# Trepanat_Sensors_2.net
KiCad netlist of a schematic drawn in Altium Designer
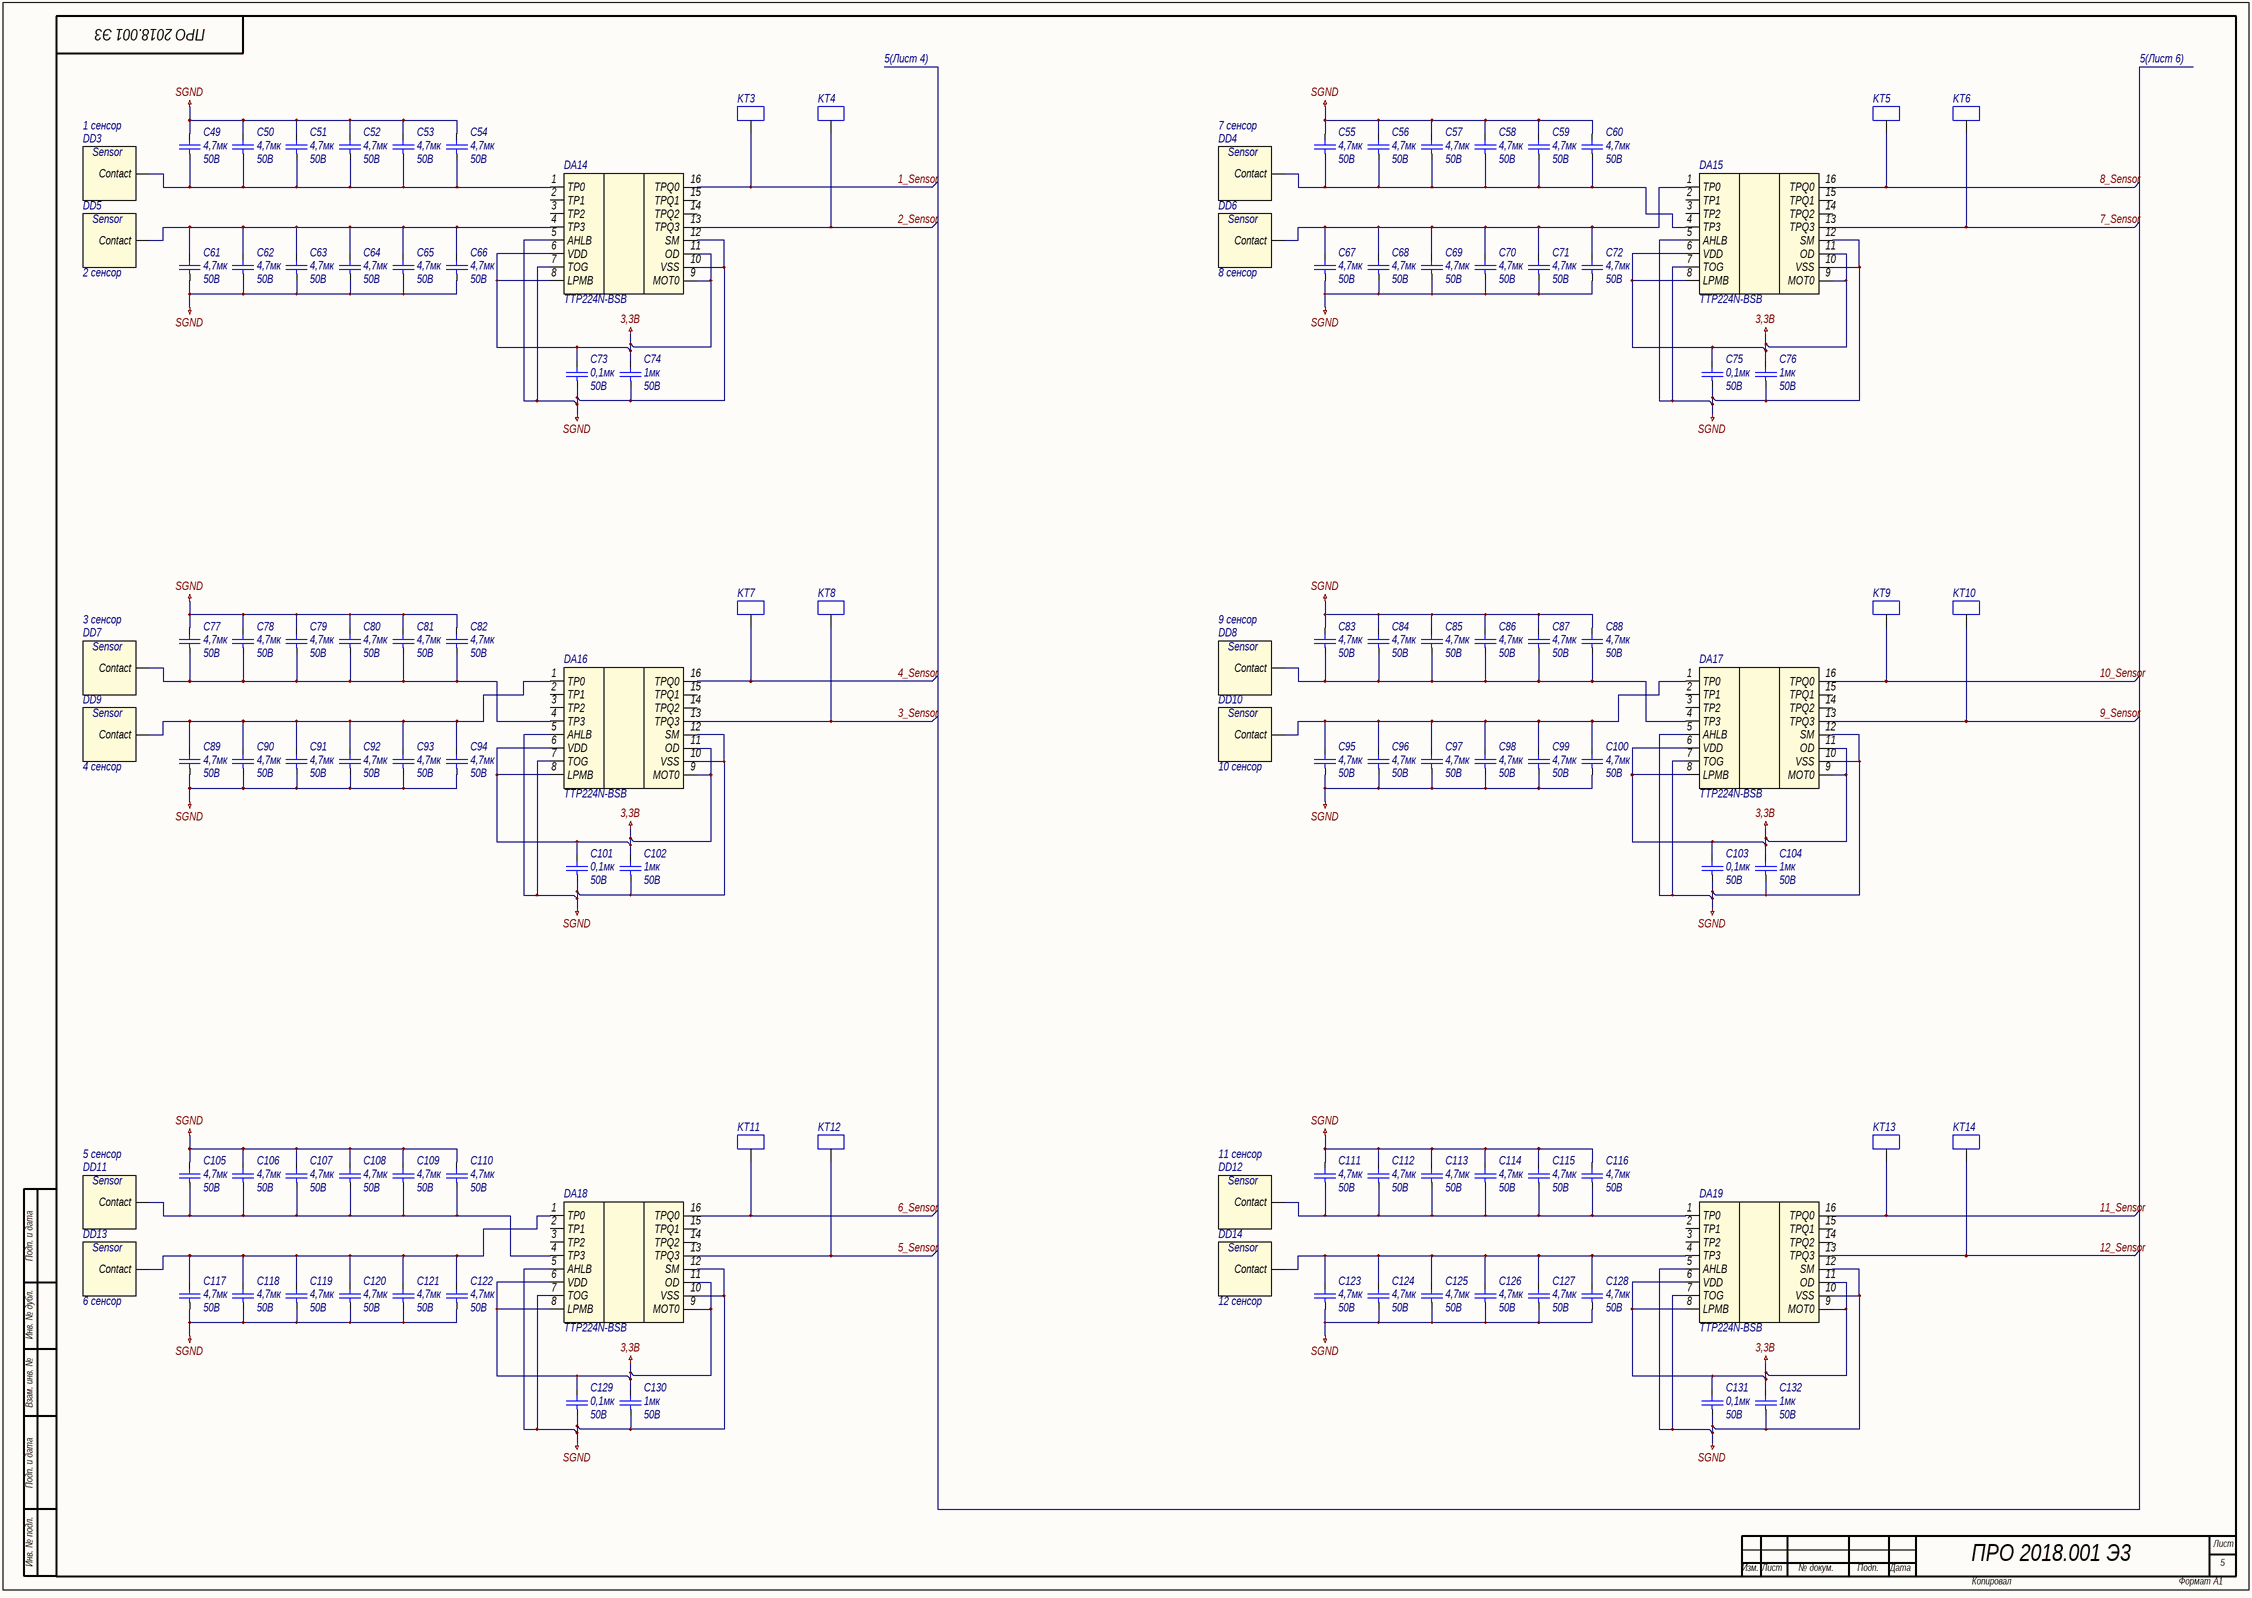
[diagram p0: Trepanat_Sensors_2.SchDoc]

(export (version "E")
  (design (tool "Eeschema 10.0.6"))
  (components
    (comp (ref "C49")
      (value "4,7мк")
      (footprint "ZabugorLib:C0805")
      (description "Конденсатор")
      (fields (field (name "VOLTAGE") "50В"))
      (libsource (lib "ZabugorLib") (part "Capacitor"))
    )
    (comp (ref "C50")
      (value "4,7мк")
      (footprint "ZabugorLib:C0805")
      (description "Конденсатор")
      (fields (field (name "VOLTAGE") "50В"))
      (libsource (lib "ZabugorLib") (part "Capacitor"))
    )
    (comp (ref "C51")
      (value "4,7мк")
      (footprint "ZabugorLib:C0805")
      (description "Конденсатор")
      (fields (field (name "VOLTAGE") "50В"))
      (libsource (lib "ZabugorLib") (part "Capacitor"))
    )
    (comp (ref "C52")
      (value "4,7мк")
      (footprint "ZabugorLib:C0805")
      (description "Конденсатор")
      (fields (field (name "VOLTAGE") "50В"))
      (libsource (lib "ZabugorLib") (part "Capacitor"))
    )
    (comp (ref "C53")
      (value "4,7мк")
      (footprint "ZabugorLib:C0805")
      (description "Конденсатор")
      (fields (field (name "VOLTAGE") "50В"))
      (libsource (lib "ZabugorLib") (part "Capacitor"))
    )
    (comp (ref "C54")
      (value "4,7мк")
      (footprint "ZabugorLib:C0805")
      (description "Конденсатор")
      (fields (field (name "VOLTAGE") "50В"))
      (libsource (lib "ZabugorLib") (part "Capacitor"))
    )
    (comp (ref "C55")
      (value "4,7мк")
      (footprint "ZabugorLib:C0805")
      (description "Конденсатор")
      (fields (field (name "VOLTAGE") "50В"))
      (libsource (lib "ZabugorLib") (part "Capacitor"))
    )
    (comp (ref "C56")
      (value "4,7мк")
      (footprint "ZabugorLib:C0805")
      (description "Конденсатор")
      (fields (field (name "VOLTAGE") "50В"))
      (libsource (lib "ZabugorLib") (part "Capacitor"))
    )
    (comp (ref "C57")
      (value "4,7мк")
      (footprint "ZabugorLib:C0805")
      (description "Конденсатор")
      (fields (field (name "VOLTAGE") "50В"))
      (libsource (lib "ZabugorLib") (part "Capacitor"))
    )
    (comp (ref "C58")
      (value "4,7мк")
      (footprint "ZabugorLib:C0805")
      (description "Конденсатор")
      (fields (field (name "VOLTAGE") "50В"))
      (libsource (lib "ZabugorLib") (part "Capacitor"))
    )
    (comp (ref "C59")
      (value "4,7мк")
      (footprint "ZabugorLib:C0805")
      (description "Конденсатор")
      (fields (field (name "VOLTAGE") "50В"))
      (libsource (lib "ZabugorLib") (part "Capacitor"))
    )
    (comp (ref "C60")
      (value "4,7мк")
      (footprint "ZabugorLib:C0805")
      (description "Конденсатор")
      (fields (field (name "VOLTAGE") "50В"))
      (libsource (lib "ZabugorLib") (part "Capacitor"))
    )
    (comp (ref "C61")
      (value "4,7мк")
      (footprint "ZabugorLib:C0805")
      (description "Конденсатор")
      (fields (field (name "VOLTAGE") "50В"))
      (libsource (lib "ZabugorLib") (part "Capacitor"))
    )
    (comp (ref "C62")
      (value "4,7мк")
      (footprint "ZabugorLib:C0805")
      (description "Конденсатор")
      (fields (field (name "VOLTAGE") "50В"))
      (libsource (lib "ZabugorLib") (part "Capacitor"))
    )
    (comp (ref "C63")
      (value "4,7мк")
      (footprint "ZabugorLib:C0805")
      (description "Конденсатор")
      (fields (field (name "VOLTAGE") "50В"))
      (libsource (lib "ZabugorLib") (part "Capacitor"))
    )
    (comp (ref "C64")
      (value "4,7мк")
      (footprint "ZabugorLib:C0805")
      (description "Конденсатор")
      (fields (field (name "VOLTAGE") "50В"))
      (libsource (lib "ZabugorLib") (part "Capacitor"))
    )
    (comp (ref "C65")
      (value "4,7мк")
      (footprint "ZabugorLib:C0805")
      (description "Конденсатор")
      (fields (field (name "VOLTAGE") "50В"))
      (libsource (lib "ZabugorLib") (part "Capacitor"))
    )
    (comp (ref "C66")
      (value "4,7мк")
      (footprint "ZabugorLib:C0805")
      (description "Конденсатор")
      (fields (field (name "VOLTAGE") "50В"))
      (libsource (lib "ZabugorLib") (part "Capacitor"))
    )
    (comp (ref "C67")
      (value "4,7мк")
      (footprint "ZabugorLib:C0805")
      (description "Конденсатор")
      (fields (field (name "VOLTAGE") "50В"))
      (libsource (lib "ZabugorLib") (part "Capacitor"))
    )
    (comp (ref "C68")
      (value "4,7мк")
      (footprint "ZabugorLib:C0805")
      (description "Конденсатор")
      (fields (field (name "VOLTAGE") "50В"))
      (libsource (lib "ZabugorLib") (part "Capacitor"))
    )
    (comp (ref "C69")
      (value "4,7мк")
      (footprint "ZabugorLib:C0805")
      (description "Конденсатор")
      (fields (field (name "VOLTAGE") "50В"))
      (libsource (lib "ZabugorLib") (part "Capacitor"))
    )
    (comp (ref "C70")
      (value "4,7мк")
      (footprint "ZabugorLib:C0805")
      (description "Конденсатор")
      (fields (field (name "VOLTAGE") "50В"))
      (libsource (lib "ZabugorLib") (part "Capacitor"))
    )
    (comp (ref "C71")
      (value "4,7мк")
      (footprint "ZabugorLib:C0805")
      (description "Конденсатор")
      (fields (field (name "VOLTAGE") "50В"))
      (libsource (lib "ZabugorLib") (part "Capacitor"))
    )
    (comp (ref "C72")
      (value "4,7мк")
      (footprint "ZabugorLib:C0805")
      (description "Конденсатор")
      (fields (field (name "VOLTAGE") "50В"))
      (libsource (lib "ZabugorLib") (part "Capacitor"))
    )
    (comp (ref "C73")
      (value "0,1мк")
      (footprint "ZabugorLib:C0805")
      (description "Конденсатор")
      (fields (field (name "VOLTAGE") "50В"))
      (libsource (lib "ZabugorLib") (part "Capacitor"))
    )
    (comp (ref "C74")
      (value "1мк")
      (footprint "ZabugorLib:C0805")
      (description "Конденсатор")
      (fields (field (name "VOLTAGE") "50В"))
      (libsource (lib "ZabugorLib") (part "Capacitor"))
    )
    (comp (ref "C75")
      (value "0,1мк")
      (footprint "ZabugorLib:C0805")
      (description "Конденсатор")
      (fields (field (name "VOLTAGE") "50В"))
      (libsource (lib "ZabugorLib") (part "Capacitor"))
    )
    (comp (ref "C76")
      (value "1мк")
      (footprint "ZabugorLib:C0805")
      (description "Конденсатор")
      (fields (field (name "VOLTAGE") "50В"))
      (libsource (lib "ZabugorLib") (part "Capacitor"))
    )
    (comp (ref "C77")
      (value "4,7мк")
      (footprint "ZabugorLib:C0805")
      (description "Конденсатор")
      (fields (field (name "VOLTAGE") "50В"))
      (libsource (lib "ZabugorLib") (part "Capacitor"))
    )
    (comp (ref "C78")
      (value "4,7мк")
      (footprint "ZabugorLib:C0805")
      (description "Конденсатор")
      (fields (field (name "VOLTAGE") "50В"))
      (libsource (lib "ZabugorLib") (part "Capacitor"))
    )
    (comp (ref "C79")
      (value "4,7мк")
      (footprint "ZabugorLib:C0805")
      (description "Конденсатор")
      (fields (field (name "VOLTAGE") "50В"))
      (libsource (lib "ZabugorLib") (part "Capacitor"))
    )
    (comp (ref "C80")
      (value "4,7мк")
      (footprint "ZabugorLib:C0805")
      (description "Конденсатор")
      (fields (field (name "VOLTAGE") "50В"))
      (libsource (lib "ZabugorLib") (part "Capacitor"))
    )
    (comp (ref "C81")
      (value "4,7мк")
      (footprint "ZabugorLib:C0805")
      (description "Конденсатор")
      (fields (field (name "VOLTAGE") "50В"))
      (libsource (lib "ZabugorLib") (part "Capacitor"))
    )
    (comp (ref "C82")
      (value "4,7мк")
      (footprint "ZabugorLib:C0805")
      (description "Конденсатор")
      (fields (field (name "VOLTAGE") "50В"))
      (libsource (lib "ZabugorLib") (part "Capacitor"))
    )
    (comp (ref "C83")
      (value "4,7мк")
      (footprint "ZabugorLib:C0805")
      (description "Конденсатор")
      (fields (field (name "VOLTAGE") "50В"))
      (libsource (lib "ZabugorLib") (part "Capacitor"))
    )
    (comp (ref "C84")
      (value "4,7мк")
      (footprint "ZabugorLib:C0805")
      (description "Конденсатор")
      (fields (field (name "VOLTAGE") "50В"))
      (libsource (lib "ZabugorLib") (part "Capacitor"))
    )
    (comp (ref "C85")
      (value "4,7мк")
      (footprint "ZabugorLib:C0805")
      (description "Конденсатор")
      (fields (field (name "VOLTAGE") "50В"))
      (libsource (lib "ZabugorLib") (part "Capacitor"))
    )
    (comp (ref "C86")
      (value "4,7мк")
      (footprint "ZabugorLib:C0805")
      (description "Конденсатор")
      (fields (field (name "VOLTAGE") "50В"))
      (libsource (lib "ZabugorLib") (part "Capacitor"))
    )
    (comp (ref "C87")
      (value "4,7мк")
      (footprint "ZabugorLib:C0805")
      (description "Конденсатор")
      (fields (field (name "VOLTAGE") "50В"))
      (libsource (lib "ZabugorLib") (part "Capacitor"))
    )
    (comp (ref "C88")
      (value "4,7мк")
      (footprint "ZabugorLib:C0805")
      (description "Конденсатор")
      (fields (field (name "VOLTAGE") "50В"))
      (libsource (lib "ZabugorLib") (part "Capacitor"))
    )
    (comp (ref "C89")
      (value "4,7мк")
      (footprint "ZabugorLib:C0805")
      (description "Конденсатор")
      (fields (field (name "VOLTAGE") "50В"))
      (libsource (lib "ZabugorLib") (part "Capacitor"))
    )
    (comp (ref "C90")
      (value "4,7мк")
      (footprint "ZabugorLib:C0805")
      (description "Конденсатор")
      (fields (field (name "VOLTAGE") "50В"))
      (libsource (lib "ZabugorLib") (part "Capacitor"))
    )
    (comp (ref "C91")
      (value "4,7мк")
      (footprint "ZabugorLib:C0805")
      (description "Конденсатор")
      (fields (field (name "VOLTAGE") "50В"))
      (libsource (lib "ZabugorLib") (part "Capacitor"))
    )
    (comp (ref "C92")
      (value "4,7мк")
      (footprint "ZabugorLib:C0805")
      (description "Конденсатор")
      (fields (field (name "VOLTAGE") "50В"))
      (libsource (lib "ZabugorLib") (part "Capacitor"))
    )
    (comp (ref "C93")
      (value "4,7мк")
      (footprint "ZabugorLib:C0805")
      (description "Конденсатор")
      (fields (field (name "VOLTAGE") "50В"))
      (libsource (lib "ZabugorLib") (part "Capacitor"))
    )
    (comp (ref "C94")
      (value "4,7мк")
      (footprint "ZabugorLib:C0805")
      (description "Конденсатор")
      (fields (field (name "VOLTAGE") "50В"))
      (libsource (lib "ZabugorLib") (part "Capacitor"))
    )
    (comp (ref "C95")
      (value "4,7мк")
      (footprint "ZabugorLib:C0805")
      (description "Конденсатор")
      (fields (field (name "VOLTAGE") "50В"))
      (libsource (lib "ZabugorLib") (part "Capacitor"))
    )
    (comp (ref "C96")
      (value "4,7мк")
      (footprint "ZabugorLib:C0805")
      (description "Конденсатор")
      (fields (field (name "VOLTAGE") "50В"))
      (libsource (lib "ZabugorLib") (part "Capacitor"))
    )
    (comp (ref "C97")
      (value "4,7мк")
      (footprint "ZabugorLib:C0805")
      (description "Конденсатор")
      (fields (field (name "VOLTAGE") "50В"))
      (libsource (lib "ZabugorLib") (part "Capacitor"))
    )
    (comp (ref "C98")
      (value "4,7мк")
      (footprint "ZabugorLib:C0805")
      (description "Конденсатор")
      (fields (field (name "VOLTAGE") "50В"))
      (libsource (lib "ZabugorLib") (part "Capacitor"))
    )
    (comp (ref "C99")
      (value "4,7мк")
      (footprint "ZabugorLib:C0805")
      (description "Конденсатор")
      (fields (field (name "VOLTAGE") "50В"))
      (libsource (lib "ZabugorLib") (part "Capacitor"))
    )
    (comp (ref "C100")
      (value "4,7мк")
      (footprint "ZabugorLib:C0805")
      (description "Конденсатор")
      (fields (field (name "VOLTAGE") "50В"))
      (libsource (lib "ZabugorLib") (part "Capacitor"))
    )
    (comp (ref "C101")
      (value "0,1мк")
      (footprint "ZabugorLib:C0805")
      (description "Конденсатор")
      (fields (field (name "VOLTAGE") "50В"))
      (libsource (lib "ZabugorLib") (part "Capacitor"))
    )
    (comp (ref "C102")
      (value "1мк")
      (footprint "ZabugorLib:C0805")
      (description "Конденсатор")
      (fields (field (name "VOLTAGE") "50В"))
      (libsource (lib "ZabugorLib") (part "Capacitor"))
    )
    (comp (ref "C103")
      (value "0,1мк")
      (footprint "ZabugorLib:C0805")
      (description "Конденсатор")
      (fields (field (name "VOLTAGE") "50В"))
      (libsource (lib "ZabugorLib") (part "Capacitor"))
    )
    (comp (ref "C104")
      (value "1мк")
      (footprint "ZabugorLib:C0805")
      (description "Конденсатор")
      (fields (field (name "VOLTAGE") "50В"))
      (libsource (lib "ZabugorLib") (part "Capacitor"))
    )
    (comp (ref "C105")
      (value "4,7мк")
      (footprint "ZabugorLib:C0805")
      (description "Конденсатор")
      (fields (field (name "VOLTAGE") "50В"))
      (libsource (lib "ZabugorLib") (part "Capacitor"))
    )
    (comp (ref "C106")
      (value "4,7мк")
      (footprint "ZabugorLib:C0805")
      (description "Конденсатор")
      (fields (field (name "VOLTAGE") "50В"))
      (libsource (lib "ZabugorLib") (part "Capacitor"))
    )
    (comp (ref "C107")
      (value "4,7мк")
      (footprint "ZabugorLib:C0805")
      (description "Конденсатор")
      (fields (field (name "VOLTAGE") "50В"))
      (libsource (lib "ZabugorLib") (part "Capacitor"))
    )
    (comp (ref "C108")
      (value "4,7мк")
      (footprint "ZabugorLib:C0805")
      (description "Конденсатор")
      (fields (field (name "VOLTAGE") "50В"))
      (libsource (lib "ZabugorLib") (part "Capacitor"))
    )
    (comp (ref "C109")
      (value "4,7мк")
      (footprint "ZabugorLib:C0805")
      (description "Конденсатор")
      (fields (field (name "VOLTAGE") "50В"))
      (libsource (lib "ZabugorLib") (part "Capacitor"))
    )
    (comp (ref "C110")
      (value "4,7мк")
      (footprint "ZabugorLib:C0805")
      (description "Конденсатор")
      (fields (field (name "VOLTAGE") "50В"))
      (libsource (lib "ZabugorLib") (part "Capacitor"))
    )
    (comp (ref "C111")
      (value "4,7мк")
      (footprint "ZabugorLib:C0805")
      (description "Конденсатор")
      (fields (field (name "VOLTAGE") "50В"))
      (libsource (lib "ZabugorLib") (part "Capacitor"))
    )
    (comp (ref "C112")
      (value "4,7мк")
      (footprint "ZabugorLib:C0805")
      (description "Конденсатор")
      (fields (field (name "VOLTAGE") "50В"))
      (libsource (lib "ZabugorLib") (part "Capacitor"))
    )
    (comp (ref "C113")
      (value "4,7мк")
      (footprint "ZabugorLib:C0805")
      (description "Конденсатор")
      (fields (field (name "VOLTAGE") "50В"))
      (libsource (lib "ZabugorLib") (part "Capacitor"))
    )
    (comp (ref "C114")
      (value "4,7мк")
      (footprint "ZabugorLib:C0805")
      (description "Конденсатор")
      (fields (field (name "VOLTAGE") "50В"))
      (libsource (lib "ZabugorLib") (part "Capacitor"))
    )
    (comp (ref "C115")
      (value "4,7мк")
      (footprint "ZabugorLib:C0805")
      (description "Конденсатор")
      (fields (field (name "VOLTAGE") "50В"))
      (libsource (lib "ZabugorLib") (part "Capacitor"))
    )
    (comp (ref "C116")
      (value "4,7мк")
      (footprint "ZabugorLib:C0805")
      (description "Конденсатор")
      (fields (field (name "VOLTAGE") "50В"))
      (libsource (lib "ZabugorLib") (part "Capacitor"))
    )
    (comp (ref "C117")
      (value "4,7мк")
      (footprint "ZabugorLib:C0805")
      (description "Конденсатор")
      (fields (field (name "VOLTAGE") "50В"))
      (libsource (lib "ZabugorLib") (part "Capacitor"))
    )
    (comp (ref "C118")
      (value "4,7мк")
      (footprint "ZabugorLib:C0805")
      (description "Конденсатор")
      (fields (field (name "VOLTAGE") "50В"))
      (libsource (lib "ZabugorLib") (part "Capacitor"))
    )
    (comp (ref "C119")
      (value "4,7мк")
      (footprint "ZabugorLib:C0805")
      (description "Конденсатор")
      (fields (field (name "VOLTAGE") "50В"))
      (libsource (lib "ZabugorLib") (part "Capacitor"))
    )
    (comp (ref "C120")
      (value "4,7мк")
      (footprint "ZabugorLib:C0805")
      (description "Конденсатор")
      (fields (field (name "VOLTAGE") "50В"))
      (libsource (lib "ZabugorLib") (part "Capacitor"))
    )
    (comp (ref "C121")
      (value "4,7мк")
      (footprint "ZabugorLib:C0805")
      (description "Конденсатор")
      (fields (field (name "VOLTAGE") "50В"))
      (libsource (lib "ZabugorLib") (part "Capacitor"))
    )
    (comp (ref "C122")
      (value "4,7мк")
      (footprint "ZabugorLib:C0805")
      (description "Конденсатор")
      (fields (field (name "VOLTAGE") "50В"))
      (libsource (lib "ZabugorLib") (part "Capacitor"))
    )
    (comp (ref "C123")
      (value "4,7мк")
      (footprint "ZabugorLib:C0805")
      (description "Конденсатор")
      (fields (field (name "VOLTAGE") "50В"))
      (libsource (lib "ZabugorLib") (part "Capacitor"))
    )
    (comp (ref "C124")
      (value "4,7мк")
      (footprint "ZabugorLib:C0805")
      (description "Конденсатор")
      (fields (field (name "VOLTAGE") "50В"))
      (libsource (lib "ZabugorLib") (part "Capacitor"))
    )
    (comp (ref "C125")
      (value "4,7мк")
      (footprint "ZabugorLib:C0805")
      (description "Конденсатор")
      (fields (field (name "VOLTAGE") "50В"))
      (libsource (lib "ZabugorLib") (part "Capacitor"))
    )
    (comp (ref "C126")
      (value "4,7мк")
      (footprint "ZabugorLib:C0805")
      (description "Конденсатор")
      (fields (field (name "VOLTAGE") "50В"))
      (libsource (lib "ZabugorLib") (part "Capacitor"))
    )
    (comp (ref "C127")
      (value "4,7мк")
      (footprint "ZabugorLib:C0805")
      (description "Конденсатор")
      (fields (field (name "VOLTAGE") "50В"))
      (libsource (lib "ZabugorLib") (part "Capacitor"))
    )
    (comp (ref "C128")
      (value "4,7мк")
      (footprint "ZabugorLib:C0805")
      (description "Конденсатор")
      (fields (field (name "VOLTAGE") "50В"))
      (libsource (lib "ZabugorLib") (part "Capacitor"))
    )
    (comp (ref "C129")
      (value "0,1мк")
      (footprint "ZabugorLib:C0805")
      (description "Конденсатор")
      (fields (field (name "VOLTAGE") "50В"))
      (libsource (lib "ZabugorLib") (part "Capacitor"))
    )
    (comp (ref "C130")
      (value "1мк")
      (footprint "ZabugorLib:C0805")
      (description "Конденсатор")
      (fields (field (name "VOLTAGE") "50В"))
      (libsource (lib "ZabugorLib") (part "Capacitor"))
    )
    (comp (ref "C131")
      (value "0,1мк")
      (footprint "ZabugorLib:C0805")
      (description "Конденсатор")
      (fields (field (name "VOLTAGE") "50В"))
      (libsource (lib "ZabugorLib") (part "Capacitor"))
    )
    (comp (ref "C132")
      (value "1мк")
      (footprint "ZabugorLib:C0805")
      (description "Конденсатор")
      (fields (field (name "VOLTAGE") "50В"))
      (libsource (lib "ZabugorLib") (part "Capacitor"))
    )
    (comp (ref "DA14")
      (value "TTP224N-BSB")
      (footprint "ZabugorLib:SSOP16")
      (description "4 keys Touch Pad Detector IC")
      (libsource (lib "ZabugorLib") (part "TTP224N-BSB"))
    )
    (comp (ref "DA15")
      (value "TTP224N-BSB")
      (footprint "ZabugorLib:SSOP16")
      (description "4 keys Touch Pad Detector IC")
      (libsource (lib "ZabugorLib") (part "TTP224N-BSB"))
    )
    (comp (ref "DA16")
      (value "TTP224N-BSB")
      (footprint "ZabugorLib:SSOP16")
      (description "4 keys Touch Pad Detector IC")
      (libsource (lib "ZabugorLib") (part "TTP224N-BSB"))
    )
    (comp (ref "DA17")
      (value "TTP224N-BSB")
      (footprint "ZabugorLib:SSOP16")
      (description "4 keys Touch Pad Detector IC")
      (libsource (lib "ZabugorLib") (part "TTP224N-BSB"))
    )
    (comp (ref "DA18")
      (value "TTP224N-BSB")
      (footprint "ZabugorLib:SSOP16")
      (description "4 keys Touch Pad Detector IC")
      (libsource (lib "ZabugorLib") (part "TTP224N-BSB"))
    )
    (comp (ref "DA19")
      (value "TTP224N-BSB")
      (footprint "ZabugorLib:SSOP16")
      (description "4 keys Touch Pad Detector IC")
      (libsource (lib "ZabugorLib") (part "TTP224N-BSB"))
    )
    (comp (ref "DD3")
      (value "1 сенсор")
      (footprint "ZabugorLib:SENSOR")
      (description "Сенсорная площадка")
      (libsource (lib "ZabugorLib") (part "Sensor"))
    )
    (comp (ref "DD4")
      (value "7 сенсор")
      (footprint "ZabugorLib:SENSOR")
      (description "Сенсорная площадка")
      (libsource (lib "ZabugorLib") (part "Sensor"))
    )
    (comp (ref "DD5")
      (value "2 сенсор")
      (footprint "ZabugorLib:SENSOR")
      (description "Сенсорная площадка")
      (libsource (lib "ZabugorLib") (part "Sensor"))
    )
    (comp (ref "DD6")
      (value "8 сенсор")
      (footprint "ZabugorLib:SENSOR")
      (description "Сенсорная площадка")
      (libsource (lib "ZabugorLib") (part "Sensor"))
    )
    (comp (ref "DD7")
      (value "3 сенсор")
      (footprint "ZabugorLib:SENSOR")
      (description "Сенсорная площадка")
      (libsource (lib "ZabugorLib") (part "Sensor"))
    )
    (comp (ref "DD8")
      (value "9 сенсор")
      (footprint "ZabugorLib:SENSOR")
      (description "Сенсорная площадка")
      (libsource (lib "ZabugorLib") (part "Sensor"))
    )
    (comp (ref "DD9")
      (value "4 сенсор")
      (footprint "ZabugorLib:SENSOR")
      (description "Сенсорная площадка")
      (libsource (lib "ZabugorLib") (part "Sensor"))
    )
    (comp (ref "DD10")
      (value "10 сенсор")
      (footprint "ZabugorLib:SENSOR")
      (description "Сенсорная площадка")
      (libsource (lib "ZabugorLib") (part "Sensor"))
    )
    (comp (ref "DD11")
      (value "5 сенсор")
      (footprint "ZabugorLib:SENSOR")
      (description "Сенсорная площадка")
      (libsource (lib "ZabugorLib") (part "Sensor"))
    )
    (comp (ref "DD12")
      (value "11 сенсор")
      (footprint "ZabugorLib:SENSOR")
      (description "Сенсорная площадка")
      (libsource (lib "ZabugorLib") (part "Sensor"))
    )
    (comp (ref "DD13")
      (value "6 сенсор")
      (footprint "ZabugorLib:SENSOR")
      (description "Сенсорная площадка")
      (libsource (lib "ZabugorLib") (part "Sensor"))
    )
    (comp (ref "DD14")
      (value "12 сенсор")
      (footprint "ZabugorLib:SENSOR")
      (description "Сенсорная площадка")
      (libsource (lib "ZabugorLib") (part "Sensor"))
    )
    (comp (ref "KT3")
      (value "KT")
      (footprint "ZabugorLib:КТ")
      (description "Контрольная точка")
      (libsource (lib "ZabugorLib") (part "KT"))
    )
    (comp (ref "KT4")
      (value "KT")
      (footprint "ZabugorLib:КТ")
      (description "Контрольная точка")
      (libsource (lib "ZabugorLib") (part "KT"))
    )
    (comp (ref "KT5")
      (value "KT")
      (footprint "ZabugorLib:КТ")
      (description "Контрольная точка")
      (libsource (lib "ZabugorLib") (part "KT"))
    )
    (comp (ref "KT6")
      (value "KT")
      (footprint "ZabugorLib:КТ")
      (description "Контрольная точка")
      (libsource (lib "ZabugorLib") (part "KT"))
    )
    (comp (ref "KT7")
      (value "KT")
      (footprint "ZabugorLib:КТ")
      (description "Контрольная точка")
      (libsource (lib "ZabugorLib") (part "KT"))
    )
    (comp (ref "KT8")
      (value "KT")
      (footprint "ZabugorLib:КТ")
      (description "Контрольная точка")
      (libsource (lib "ZabugorLib") (part "KT"))
    )
    (comp (ref "KT9")
      (value "KT")
      (footprint "ZabugorLib:КТ")
      (description "Контрольная точка")
      (libsource (lib "ZabugorLib") (part "KT"))
    )
    (comp (ref "KT10")
      (value "KT")
      (footprint "ZabugorLib:КТ")
      (description "Контрольная точка")
      (libsource (lib "ZabugorLib") (part "KT"))
    )
    (comp (ref "KT11")
      (value "KT")
      (footprint "ZabugorLib:КТ")
      (description "Контрольная точка")
      (libsource (lib "ZabugorLib") (part "KT"))
    )
    (comp (ref "KT12")
      (value "KT")
      (footprint "ZabugorLib:КТ")
      (description "Контрольная точка")
      (libsource (lib "ZabugorLib") (part "KT"))
    )
    (comp (ref "KT13")
      (value "KT")
      (footprint "ZabugorLib:КТ")
      (description "Контрольная точка")
      (libsource (lib "ZabugorLib") (part "KT"))
    )
    (comp (ref "KT14")
      (value "KT")
      (footprint "ZabugorLib:КТ")
      (description "Контрольная точка")
      (libsource (lib "ZabugorLib") (part "KT"))
    )
  )
  (nets
    (net (code "1") (name "/1_Sensor") (class "Default")
      (node (ref "DA14") (pin "16") (pinfunction "TPQ0_16") (pintype "power_in"))
      (node (ref "KT3") (pin "1") (pinfunction "1_1") (pintype "passive"))
    )
    (net (code "2") (name "/2_Sensor") (class "Default")
      (node (ref "DA14") (pin "13") (pinfunction "TPQ3_13") (pintype "power_in"))
      (node (ref "KT4") (pin "1") (pinfunction "1_1") (pintype "passive"))
    )
    (net (code "3") (name "/3_Sensor") (class "Default")
      (node (ref "DA16") (pin "13") (pinfunction "TPQ3_13") (pintype "power_in"))
      (node (ref "KT8") (pin "1") (pinfunction "1_1") (pintype "passive"))
    )
    (net (code "4") (name "/4_Sensor") (class "Default")
      (node (ref "DA16") (pin "16") (pinfunction "TPQ0_16") (pintype "power_in"))
      (node (ref "KT7") (pin "1") (pinfunction "1_1") (pintype "passive"))
    )
    (net (code "5") (name "/5_Sensor") (class "Default")
      (node (ref "DA18") (pin "13") (pinfunction "TPQ3_13") (pintype "power_in"))
      (node (ref "KT12") (pin "1") (pinfunction "1_1") (pintype "passive"))
    )
    (net (code "6") (name "/6_Sensor") (class "Default")
      (node (ref "DA18") (pin "16") (pinfunction "TPQ0_16") (pintype "power_in"))
      (node (ref "KT11") (pin "1") (pinfunction "1_1") (pintype "passive"))
    )
    (net (code "7") (name "/7_Sensor") (class "Default")
      (node (ref "DA15") (pin "13") (pinfunction "TPQ3_13") (pintype "power_in"))
      (node (ref "KT6") (pin "1") (pinfunction "1_1") (pintype "passive"))
    )
    (net (code "8") (name "/8_Sensor") (class "Default")
      (node (ref "DA15") (pin "16") (pinfunction "TPQ0_16") (pintype "power_in"))
      (node (ref "KT5") (pin "1") (pinfunction "1_1") (pintype "passive"))
    )
    (net (code "9") (name "/9_Sensor") (class "Default")
      (node (ref "DA17") (pin "13") (pinfunction "TPQ3_13") (pintype "power_in"))
      (node (ref "KT10") (pin "1") (pinfunction "1_1") (pintype "passive"))
    )
    (net (code "10") (name "/10_Sensor") (class "Default")
      (node (ref "DA17") (pin "16") (pinfunction "TPQ0_16") (pintype "power_in"))
      (node (ref "KT9") (pin "1") (pinfunction "1_1") (pintype "passive"))
    )
    (net (code "11") (name "/11_Sensor") (class "Default")
      (node (ref "DA19") (pin "16") (pinfunction "TPQ0_16") (pintype "power_in"))
      (node (ref "KT13") (pin "1") (pinfunction "1_1") (pintype "passive"))
    )
    (net (code "12") (name "/12_Sensor") (class "Default")
      (node (ref "DA19") (pin "13") (pinfunction "TPQ3_13") (pintype "power_in"))
      (node (ref "KT14") (pin "1") (pinfunction "1_1") (pintype "passive"))
    )
    (net (code "13") (name "3,3B") (class "Default")
      (node (ref "C101") (pin "2") (pinfunction "2_2") (pintype "passive"))
      (node (ref "C102") (pin "2") (pinfunction "2_2") (pintype "passive"))
      (node (ref "C103") (pin "2") (pinfunction "2_2") (pintype "passive"))
      (node (ref "C104") (pin "2") (pinfunction "2_2") (pintype "passive"))
      (node (ref "C129") (pin "2") (pinfunction "2_2") (pintype "passive"))
      (node (ref "C130") (pin "2") (pinfunction "2_2") (pintype "passive"))
      (node (ref "C131") (pin "2") (pinfunction "2_2") (pintype "passive"))
      (node (ref "C132") (pin "2") (pinfunction "2_2") (pintype "passive"))
      (node (ref "C73") (pin "2") (pinfunction "2_2") (pintype "passive"))
      (node (ref "C74") (pin "2") (pinfunction "2_2") (pintype "passive"))
      (node (ref "C75") (pin "2") (pinfunction "2_2") (pintype "passive"))
      (node (ref "C76") (pin "2") (pinfunction "2_2") (pintype "passive"))
      (node (ref "DA14") (pin "11") (pinfunction "OD_11") (pintype "power_in"))
      (node (ref "DA14") (pin "6") (pinfunction "VDD_6") (pintype "power_in"))
      (node (ref "DA14") (pin "8") (pinfunction "LPMB_8") (pintype "power_in"))
      (node (ref "DA14") (pin "9") (pinfunction "MOT0_9") (pintype "power_in"))
      (node (ref "DA15") (pin "11") (pinfunction "OD_11") (pintype "power_in"))
      (node (ref "DA15") (pin "6") (pinfunction "VDD_6") (pintype "power_in"))
      (node (ref "DA15") (pin "8") (pinfunction "LPMB_8") (pintype "power_in"))
      (node (ref "DA15") (pin "9") (pinfunction "MOT0_9") (pintype "power_in"))
      (node (ref "DA16") (pin "11") (pinfunction "OD_11") (pintype "power_in"))
      (node (ref "DA16") (pin "6") (pinfunction "VDD_6") (pintype "power_in"))
      (node (ref "DA16") (pin "8") (pinfunction "LPMB_8") (pintype "power_in"))
      (node (ref "DA16") (pin "9") (pinfunction "MOT0_9") (pintype "power_in"))
      (node (ref "DA17") (pin "11") (pinfunction "OD_11") (pintype "power_in"))
      (node (ref "DA17") (pin "6") (pinfunction "VDD_6") (pintype "power_in"))
      (node (ref "DA17") (pin "8") (pinfunction "LPMB_8") (pintype "power_in"))
      (node (ref "DA17") (pin "9") (pinfunction "MOT0_9") (pintype "power_in"))
      (node (ref "DA18") (pin "11") (pinfunction "OD_11") (pintype "power_in"))
      (node (ref "DA18") (pin "6") (pinfunction "VDD_6") (pintype "power_in"))
      (node (ref "DA18") (pin "8") (pinfunction "LPMB_8") (pintype "power_in"))
      (node (ref "DA18") (pin "9") (pinfunction "MOT0_9") (pintype "power_in"))
      (node (ref "DA19") (pin "11") (pinfunction "OD_11") (pintype "power_in"))
      (node (ref "DA19") (pin "6") (pinfunction "VDD_6") (pintype "power_in"))
      (node (ref "DA19") (pin "8") (pinfunction "LPMB_8") (pintype "power_in"))
      (node (ref "DA19") (pin "9") (pinfunction "MOT0_9") (pintype "power_in"))
    )
    (net (code "14") (name "Net-(DA14-TP0)") (class "Default")
      (node (ref "C49") (pin "1") (pinfunction "1_1") (pintype "passive"))
      (node (ref "C50") (pin "1") (pinfunction "1_1") (pintype "passive"))
      (node (ref "C51") (pin "1") (pinfunction "1_1") (pintype "passive"))
      (node (ref "C52") (pin "1") (pinfunction "1_1") (pintype "passive"))
      (node (ref "C53") (pin "1") (pinfunction "1_1") (pintype "passive"))
      (node (ref "C54") (pin "1") (pinfunction "1_1") (pintype "passive"))
      (node (ref "DA14") (pin "1") (pinfunction "TP0_1") (pintype "power_in"))
      (node (ref "DD3") (pin "1") (pinfunction "Contact_1") (pintype "power_in"))
    )
    (net (code "15") (name "Net-(DA14-TP3)") (class "Default")
      (node (ref "C61") (pin "2") (pinfunction "2_2") (pintype "passive"))
      (node (ref "C62") (pin "2") (pinfunction "2_2") (pintype "passive"))
      (node (ref "C63") (pin "2") (pinfunction "2_2") (pintype "passive"))
      (node (ref "C64") (pin "2") (pinfunction "2_2") (pintype "passive"))
      (node (ref "C65") (pin "2") (pinfunction "2_2") (pintype "passive"))
      (node (ref "C66") (pin "2") (pinfunction "2_2") (pintype "passive"))
      (node (ref "DA14") (pin "4") (pinfunction "TP3_4") (pintype "power_in"))
      (node (ref "DD5") (pin "1") (pinfunction "Contact_1") (pintype "power_in"))
    )
    (net (code "16") (name "Net-(DA15-TP0)") (class "Default")
      (node (ref "C67") (pin "2") (pinfunction "2_2") (pintype "passive"))
      (node (ref "C68") (pin "2") (pinfunction "2_2") (pintype "passive"))
      (node (ref "C69") (pin "2") (pinfunction "2_2") (pintype "passive"))
      (node (ref "C70") (pin "2") (pinfunction "2_2") (pintype "passive"))
      (node (ref "C71") (pin "2") (pinfunction "2_2") (pintype "passive"))
      (node (ref "C72") (pin "2") (pinfunction "2_2") (pintype "passive"))
      (node (ref "DA15") (pin "1") (pinfunction "TP0_1") (pintype "power_in"))
      (node (ref "DD6") (pin "1") (pinfunction "Contact_1") (pintype "power_in"))
    )
    (net (code "17") (name "Net-(DA15-TP3)") (class "Default")
      (node (ref "C55") (pin "1") (pinfunction "1_1") (pintype "passive"))
      (node (ref "C56") (pin "1") (pinfunction "1_1") (pintype "passive"))
      (node (ref "C57") (pin "1") (pinfunction "1_1") (pintype "passive"))
      (node (ref "C58") (pin "1") (pinfunction "1_1") (pintype "passive"))
      (node (ref "C59") (pin "1") (pinfunction "1_1") (pintype "passive"))
      (node (ref "C60") (pin "1") (pinfunction "1_1") (pintype "passive"))
      (node (ref "DA15") (pin "4") (pinfunction "TP3_4") (pintype "power_in"))
      (node (ref "DD4") (pin "1") (pinfunction "Contact_1") (pintype "power_in"))
    )
    (net (code "18") (name "Net-(DA16-TP0)") (class "Default")
      (node (ref "C89") (pin "2") (pinfunction "2_2") (pintype "passive"))
      (node (ref "C90") (pin "2") (pinfunction "2_2") (pintype "passive"))
      (node (ref "C91") (pin "2") (pinfunction "2_2") (pintype "passive"))
      (node (ref "C92") (pin "2") (pinfunction "2_2") (pintype "passive"))
      (node (ref "C93") (pin "2") (pinfunction "2_2") (pintype "passive"))
      (node (ref "C94") (pin "2") (pinfunction "2_2") (pintype "passive"))
      (node (ref "DA16") (pin "1") (pinfunction "TP0_1") (pintype "power_in"))
      (node (ref "DD9") (pin "1") (pinfunction "Contact_1") (pintype "power_in"))
    )
    (net (code "19") (name "Net-(DA16-TP3)") (class "Default")
      (node (ref "C77") (pin "1") (pinfunction "1_1") (pintype "passive"))
      (node (ref "C78") (pin "1") (pinfunction "1_1") (pintype "passive"))
      (node (ref "C79") (pin "1") (pinfunction "1_1") (pintype "passive"))
      (node (ref "C80") (pin "1") (pinfunction "1_1") (pintype "passive"))
      (node (ref "C81") (pin "1") (pinfunction "1_1") (pintype "passive"))
      (node (ref "C82") (pin "1") (pinfunction "1_1") (pintype "passive"))
      (node (ref "DA16") (pin "4") (pinfunction "TP3_4") (pintype "power_in"))
      (node (ref "DD7") (pin "1") (pinfunction "Contact_1") (pintype "power_in"))
    )
    (net (code "20") (name "Net-(DA17-TP0)") (class "Default")
      (node (ref "C100") (pin "2") (pinfunction "2_2") (pintype "passive"))
      (node (ref "C95") (pin "2") (pinfunction "2_2") (pintype "passive"))
      (node (ref "C96") (pin "2") (pinfunction "2_2") (pintype "passive"))
      (node (ref "C97") (pin "2") (pinfunction "2_2") (pintype "passive"))
      (node (ref "C98") (pin "2") (pinfunction "2_2") (pintype "passive"))
      (node (ref "C99") (pin "2") (pinfunction "2_2") (pintype "passive"))
      (node (ref "DA17") (pin "1") (pinfunction "TP0_1") (pintype "power_in"))
      (node (ref "DD10") (pin "1") (pinfunction "Contact_1") (pintype "power_in"))
    )
    (net (code "21") (name "Net-(DA17-TP3)") (class "Default")
      (node (ref "C83") (pin "1") (pinfunction "1_1") (pintype "passive"))
      (node (ref "C84") (pin "1") (pinfunction "1_1") (pintype "passive"))
      (node (ref "C85") (pin "1") (pinfunction "1_1") (pintype "passive"))
      (node (ref "C86") (pin "1") (pinfunction "1_1") (pintype "passive"))
      (node (ref "C87") (pin "1") (pinfunction "1_1") (pintype "passive"))
      (node (ref "C88") (pin "1") (pinfunction "1_1") (pintype "passive"))
      (node (ref "DA17") (pin "4") (pinfunction "TP3_4") (pintype "power_in"))
      (node (ref "DD8") (pin "1") (pinfunction "Contact_1") (pintype "power_in"))
    )
    (net (code "22") (name "Net-(DA18-TP0)") (class "Default")
      (node (ref "C117") (pin "2") (pinfunction "2_2") (pintype "passive"))
      (node (ref "C118") (pin "2") (pinfunction "2_2") (pintype "passive"))
      (node (ref "C119") (pin "2") (pinfunction "2_2") (pintype "passive"))
      (node (ref "C120") (pin "2") (pinfunction "2_2") (pintype "passive"))
      (node (ref "C121") (pin "2") (pinfunction "2_2") (pintype "passive"))
      (node (ref "C122") (pin "2") (pinfunction "2_2") (pintype "passive"))
      (node (ref "DA18") (pin "1") (pinfunction "TP0_1") (pintype "power_in"))
      (node (ref "DD13") (pin "1") (pinfunction "Contact_1") (pintype "power_in"))
    )
    (net (code "23") (name "Net-(DA18-TP3)") (class "Default")
      (node (ref "C105") (pin "1") (pinfunction "1_1") (pintype "passive"))
      (node (ref "C106") (pin "1") (pinfunction "1_1") (pintype "passive"))
      (node (ref "C107") (pin "1") (pinfunction "1_1") (pintype "passive"))
      (node (ref "C108") (pin "1") (pinfunction "1_1") (pintype "passive"))
      (node (ref "C109") (pin "1") (pinfunction "1_1") (pintype "passive"))
      (node (ref "C110") (pin "1") (pinfunction "1_1") (pintype "passive"))
      (node (ref "DA18") (pin "4") (pinfunction "TP3_4") (pintype "power_in"))
      (node (ref "DD11") (pin "1") (pinfunction "Contact_1") (pintype "power_in"))
    )
    (net (code "24") (name "Net-(DA19-TP0)") (class "Default")
      (node (ref "C111") (pin "1") (pinfunction "1_1") (pintype "passive"))
      (node (ref "C112") (pin "1") (pinfunction "1_1") (pintype "passive"))
      (node (ref "C113") (pin "1") (pinfunction "1_1") (pintype "passive"))
      (node (ref "C114") (pin "1") (pinfunction "1_1") (pintype "passive"))
      (node (ref "C115") (pin "1") (pinfunction "1_1") (pintype "passive"))
      (node (ref "C116") (pin "1") (pinfunction "1_1") (pintype "passive"))
      (node (ref "DA19") (pin "1") (pinfunction "TP0_1") (pintype "power_in"))
      (node (ref "DD12") (pin "1") (pinfunction "Contact_1") (pintype "power_in"))
    )
    (net (code "25") (name "Net-(DA19-TP3)") (class "Default")
      (node (ref "C123") (pin "2") (pinfunction "2_2") (pintype "passive"))
      (node (ref "C124") (pin "2") (pinfunction "2_2") (pintype "passive"))
      (node (ref "C125") (pin "2") (pinfunction "2_2") (pintype "passive"))
      (node (ref "C126") (pin "2") (pinfunction "2_2") (pintype "passive"))
      (node (ref "C127") (pin "2") (pinfunction "2_2") (pintype "passive"))
      (node (ref "C128") (pin "2") (pinfunction "2_2") (pintype "passive"))
      (node (ref "DA19") (pin "4") (pinfunction "TP3_4") (pintype "power_in"))
      (node (ref "DD14") (pin "1") (pinfunction "Contact_1") (pintype "power_in"))
    )
    (net (code "26") (name "SGND") (class "Default")
      (node (ref "C100") (pin "1") (pinfunction "1_1") (pintype "passive"))
      (node (ref "C101") (pin "1") (pinfunction "1_1") (pintype "passive"))
      (node (ref "C102") (pin "1") (pinfunction "1_1") (pintype "passive"))
      (node (ref "C103") (pin "1") (pinfunction "1_1") (pintype "passive"))
      (node (ref "C104") (pin "1") (pinfunction "1_1") (pintype "passive"))
      (node (ref "C105") (pin "2") (pinfunction "2_2") (pintype "passive"))
      (node (ref "C106") (pin "2") (pinfunction "2_2") (pintype "passive"))
      (node (ref "C107") (pin "2") (pinfunction "2_2") (pintype "passive"))
      (node (ref "C108") (pin "2") (pinfunction "2_2") (pintype "passive"))
      (node (ref "C109") (pin "2") (pinfunction "2_2") (pintype "passive"))
      (node (ref "C110") (pin "2") (pinfunction "2_2") (pintype "passive"))
      (node (ref "C111") (pin "2") (pinfunction "2_2") (pintype "passive"))
      (node (ref "C112") (pin "2") (pinfunction "2_2") (pintype "passive"))
      (node (ref "C113") (pin "2") (pinfunction "2_2") (pintype "passive"))
      (node (ref "C114") (pin "2") (pinfunction "2_2") (pintype "passive"))
      (node (ref "C115") (pin "2") (pinfunction "2_2") (pintype "passive"))
      (node (ref "C116") (pin "2") (pinfunction "2_2") (pintype "passive"))
      (node (ref "C117") (pin "1") (pinfunction "1_1") (pintype "passive"))
      (node (ref "C118") (pin "1") (pinfunction "1_1") (pintype "passive"))
      (node (ref "C119") (pin "1") (pinfunction "1_1") (pintype "passive"))
      (node (ref "C120") (pin "1") (pinfunction "1_1") (pintype "passive"))
      (node (ref "C121") (pin "1") (pinfunction "1_1") (pintype "passive"))
      (node (ref "C122") (pin "1") (pinfunction "1_1") (pintype "passive"))
      (node (ref "C123") (pin "1") (pinfunction "1_1") (pintype "passive"))
      (node (ref "C124") (pin "1") (pinfunction "1_1") (pintype "passive"))
      (node (ref "C125") (pin "1") (pinfunction "1_1") (pintype "passive"))
      (node (ref "C126") (pin "1") (pinfunction "1_1") (pintype "passive"))
      (node (ref "C127") (pin "1") (pinfunction "1_1") (pintype "passive"))
      (node (ref "C128") (pin "1") (pinfunction "1_1") (pintype "passive"))
      (node (ref "C129") (pin "1") (pinfunction "1_1") (pintype "passive"))
      (node (ref "C130") (pin "1") (pinfunction "1_1") (pintype "passive"))
      (node (ref "C131") (pin "1") (pinfunction "1_1") (pintype "passive"))
      (node (ref "C132") (pin "1") (pinfunction "1_1") (pintype "passive"))
      (node (ref "C49") (pin "2") (pinfunction "2_2") (pintype "passive"))
      (node (ref "C50") (pin "2") (pinfunction "2_2") (pintype "passive"))
      (node (ref "C51") (pin "2") (pinfunction "2_2") (pintype "passive"))
      (node (ref "C52") (pin "2") (pinfunction "2_2") (pintype "passive"))
      (node (ref "C53") (pin "2") (pinfunction "2_2") (pintype "passive"))
      (node (ref "C54") (pin "2") (pinfunction "2_2") (pintype "passive"))
      (node (ref "C55") (pin "2") (pinfunction "2_2") (pintype "passive"))
      (node (ref "C56") (pin "2") (pinfunction "2_2") (pintype "passive"))
      (node (ref "C57") (pin "2") (pinfunction "2_2") (pintype "passive"))
      (node (ref "C58") (pin "2") (pinfunction "2_2") (pintype "passive"))
      (node (ref "C59") (pin "2") (pinfunction "2_2") (pintype "passive"))
      (node (ref "C60") (pin "2") (pinfunction "2_2") (pintype "passive"))
      (node (ref "C61") (pin "1") (pinfunction "1_1") (pintype "passive"))
      (node (ref "C62") (pin "1") (pinfunction "1_1") (pintype "passive"))
      (node (ref "C63") (pin "1") (pinfunction "1_1") (pintype "passive"))
      (node (ref "C64") (pin "1") (pinfunction "1_1") (pintype "passive"))
      (node (ref "C65") (pin "1") (pinfunction "1_1") (pintype "passive"))
      (node (ref "C66") (pin "1") (pinfunction "1_1") (pintype "passive"))
      (node (ref "C67") (pin "1") (pinfunction "1_1") (pintype "passive"))
      (node (ref "C68") (pin "1") (pinfunction "1_1") (pintype "passive"))
      (node (ref "C69") (pin "1") (pinfunction "1_1") (pintype "passive"))
      (node (ref "C70") (pin "1") (pinfunction "1_1") (pintype "passive"))
      (node (ref "C71") (pin "1") (pinfunction "1_1") (pintype "passive"))
      (node (ref "C72") (pin "1") (pinfunction "1_1") (pintype "passive"))
      (node (ref "C73") (pin "1") (pinfunction "1_1") (pintype "passive"))
      (node (ref "C74") (pin "1") (pinfunction "1_1") (pintype "passive"))
      (node (ref "C75") (pin "1") (pinfunction "1_1") (pintype "passive"))
      (node (ref "C76") (pin "1") (pinfunction "1_1") (pintype "passive"))
      (node (ref "C77") (pin "2") (pinfunction "2_2") (pintype "passive"))
      (node (ref "C78") (pin "2") (pinfunction "2_2") (pintype "passive"))
      (node (ref "C79") (pin "2") (pinfunction "2_2") (pintype "passive"))
      (node (ref "C80") (pin "2") (pinfunction "2_2") (pintype "passive"))
      (node (ref "C81") (pin "2") (pinfunction "2_2") (pintype "passive"))
      (node (ref "C82") (pin "2") (pinfunction "2_2") (pintype "passive"))
      (node (ref "C83") (pin "2") (pinfunction "2_2") (pintype "passive"))
      (node (ref "C84") (pin "2") (pinfunction "2_2") (pintype "passive"))
      (node (ref "C85") (pin "2") (pinfunction "2_2") (pintype "passive"))
      (node (ref "C86") (pin "2") (pinfunction "2_2") (pintype "passive"))
      (node (ref "C87") (pin "2") (pinfunction "2_2") (pintype "passive"))
      (node (ref "C88") (pin "2") (pinfunction "2_2") (pintype "passive"))
      (node (ref "C89") (pin "1") (pinfunction "1_1") (pintype "passive"))
      (node (ref "C90") (pin "1") (pinfunction "1_1") (pintype "passive"))
      (node (ref "C91") (pin "1") (pinfunction "1_1") (pintype "passive"))
      (node (ref "C92") (pin "1") (pinfunction "1_1") (pintype "passive"))
      (node (ref "C93") (pin "1") (pinfunction "1_1") (pintype "passive"))
      (node (ref "C94") (pin "1") (pinfunction "1_1") (pintype "passive"))
      (node (ref "C95") (pin "1") (pinfunction "1_1") (pintype "passive"))
      (node (ref "C96") (pin "1") (pinfunction "1_1") (pintype "passive"))
      (node (ref "C97") (pin "1") (pinfunction "1_1") (pintype "passive"))
      (node (ref "C98") (pin "1") (pinfunction "1_1") (pintype "passive"))
      (node (ref "C99") (pin "1") (pinfunction "1_1") (pintype "passive"))
      (node (ref "DA14") (pin "10") (pinfunction "VSS_10") (pintype "power_in"))
      (node (ref "DA14") (pin "12") (pinfunction "SM_12") (pintype "power_in"))
      (node (ref "DA14") (pin "5") (pinfunction "AHLB_5") (pintype "power_in"))
      (node (ref "DA14") (pin "7") (pinfunction "TOG_7") (pintype "power_in"))
      (node (ref "DA15") (pin "10") (pinfunction "VSS_10") (pintype "power_in"))
      (node (ref "DA15") (pin "12") (pinfunction "SM_12") (pintype "power_in"))
      (node (ref "DA15") (pin "5") (pinfunction "AHLB_5") (pintype "power_in"))
      (node (ref "DA15") (pin "7") (pinfunction "TOG_7") (pintype "power_in"))
      (node (ref "DA16") (pin "10") (pinfunction "VSS_10") (pintype "power_in"))
      (node (ref "DA16") (pin "12") (pinfunction "SM_12") (pintype "power_in"))
      (node (ref "DA16") (pin "5") (pinfunction "AHLB_5") (pintype "power_in"))
      (node (ref "DA16") (pin "7") (pinfunction "TOG_7") (pintype "power_in"))
      (node (ref "DA17") (pin "10") (pinfunction "VSS_10") (pintype "power_in"))
      (node (ref "DA17") (pin "12") (pinfunction "SM_12") (pintype "power_in"))
      (node (ref "DA17") (pin "5") (pinfunction "AHLB_5") (pintype "power_in"))
      (node (ref "DA17") (pin "7") (pinfunction "TOG_7") (pintype "power_in"))
      (node (ref "DA18") (pin "10") (pinfunction "VSS_10") (pintype "power_in"))
      (node (ref "DA18") (pin "12") (pinfunction "SM_12") (pintype "power_in"))
      (node (ref "DA18") (pin "5") (pinfunction "AHLB_5") (pintype "power_in"))
      (node (ref "DA18") (pin "7") (pinfunction "TOG_7") (pintype "power_in"))
      (node (ref "DA19") (pin "10") (pinfunction "VSS_10") (pintype "power_in"))
      (node (ref "DA19") (pin "12") (pinfunction "SM_12") (pintype "power_in"))
      (node (ref "DA19") (pin "5") (pinfunction "AHLB_5") (pintype "power_in"))
      (node (ref "DA19") (pin "7") (pinfunction "TOG_7") (pintype "power_in"))
    )
    (net (code "27") (name "unconnected-(DA14-TP1-Pad2)") (class "Default")
      (node (ref "DA14") (pin "2") (pinfunction "TP1_2") (pintype "power_in"))
    )
    (net (code "28") (name "unconnected-(DA14-TP2-Pad3)") (class "Default")
      (node (ref "DA14") (pin "3") (pinfunction "TP2_3") (pintype "power_in"))
    )
    (net (code "29") (name "unconnected-(DA14-TPQ1-Pad15)") (class "Default")
      (node (ref "DA14") (pin "15") (pinfunction "TPQ1_15") (pintype "power_in"))
    )
    (net (code "30") (name "unconnected-(DA14-TPQ2-Pad14)") (class "Default")
      (node (ref "DA14") (pin "14") (pinfunction "TPQ2_14") (pintype "power_in"))
    )
    (net (code "31") (name "unconnected-(DA15-TP1-Pad2)") (class "Default")
      (node (ref "DA15") (pin "2") (pinfunction "TP1_2") (pintype "power_in"))
    )
    (net (code "32") (name "unconnected-(DA15-TP2-Pad3)") (class "Default")
      (node (ref "DA15") (pin "3") (pinfunction "TP2_3") (pintype "power_in"))
    )
    (net (code "33") (name "unconnected-(DA15-TPQ1-Pad15)") (class "Default")
      (node (ref "DA15") (pin "15") (pinfunction "TPQ1_15") (pintype "power_in"))
    )
    (net (code "34") (name "unconnected-(DA15-TPQ2-Pad14)") (class "Default")
      (node (ref "DA15") (pin "14") (pinfunction "TPQ2_14") (pintype "power_in"))
    )
    (net (code "35") (name "unconnected-(DA16-TP1-Pad2)") (class "Default")
      (node (ref "DA16") (pin "2") (pinfunction "TP1_2") (pintype "power_in"))
    )
    (net (code "36") (name "unconnected-(DA16-TP2-Pad3)") (class "Default")
      (node (ref "DA16") (pin "3") (pinfunction "TP2_3") (pintype "power_in"))
    )
    (net (code "37") (name "unconnected-(DA16-TPQ1-Pad15)") (class "Default")
      (node (ref "DA16") (pin "15") (pinfunction "TPQ1_15") (pintype "power_in"))
    )
    (net (code "38") (name "unconnected-(DA16-TPQ2-Pad14)") (class "Default")
      (node (ref "DA16") (pin "14") (pinfunction "TPQ2_14") (pintype "power_in"))
    )
    (net (code "39") (name "unconnected-(DA17-TP1-Pad2)") (class "Default")
      (node (ref "DA17") (pin "2") (pinfunction "TP1_2") (pintype "power_in"))
    )
    (net (code "40") (name "unconnected-(DA17-TP2-Pad3)") (class "Default")
      (node (ref "DA17") (pin "3") (pinfunction "TP2_3") (pintype "power_in"))
    )
    (net (code "41") (name "unconnected-(DA17-TPQ1-Pad15)") (class "Default")
      (node (ref "DA17") (pin "15") (pinfunction "TPQ1_15") (pintype "power_in"))
    )
    (net (code "42") (name "unconnected-(DA17-TPQ2-Pad14)") (class "Default")
      (node (ref "DA17") (pin "14") (pinfunction "TPQ2_14") (pintype "power_in"))
    )
    (net (code "43") (name "unconnected-(DA18-TP1-Pad2)") (class "Default")
      (node (ref "DA18") (pin "2") (pinfunction "TP1_2") (pintype "power_in"))
    )
    (net (code "44") (name "unconnected-(DA18-TP2-Pad3)") (class "Default")
      (node (ref "DA18") (pin "3") (pinfunction "TP2_3") (pintype "power_in"))
    )
    (net (code "45") (name "unconnected-(DA18-TPQ1-Pad15)") (class "Default")
      (node (ref "DA18") (pin "15") (pinfunction "TPQ1_15") (pintype "power_in"))
    )
    (net (code "46") (name "unconnected-(DA18-TPQ2-Pad14)") (class "Default")
      (node (ref "DA18") (pin "14") (pinfunction "TPQ2_14") (pintype "power_in"))
    )
    (net (code "47") (name "unconnected-(DA19-TP1-Pad2)") (class "Default")
      (node (ref "DA19") (pin "2") (pinfunction "TP1_2") (pintype "power_in"))
    )
    (net (code "48") (name "unconnected-(DA19-TP2-Pad3)") (class "Default")
      (node (ref "DA19") (pin "3") (pinfunction "TP2_3") (pintype "power_in"))
    )
    (net (code "49") (name "unconnected-(DA19-TPQ1-Pad15)") (class "Default")
      (node (ref "DA19") (pin "15") (pinfunction "TPQ1_15") (pintype "power_in"))
    )
    (net (code "50") (name "unconnected-(DA19-TPQ2-Pad14)") (class "Default")
      (node (ref "DA19") (pin "14") (pinfunction "TPQ2_14") (pintype "power_in"))
    )
  )
)
